# LoRa.net
KiCad netlist of a schematic drawn in Altium Designer
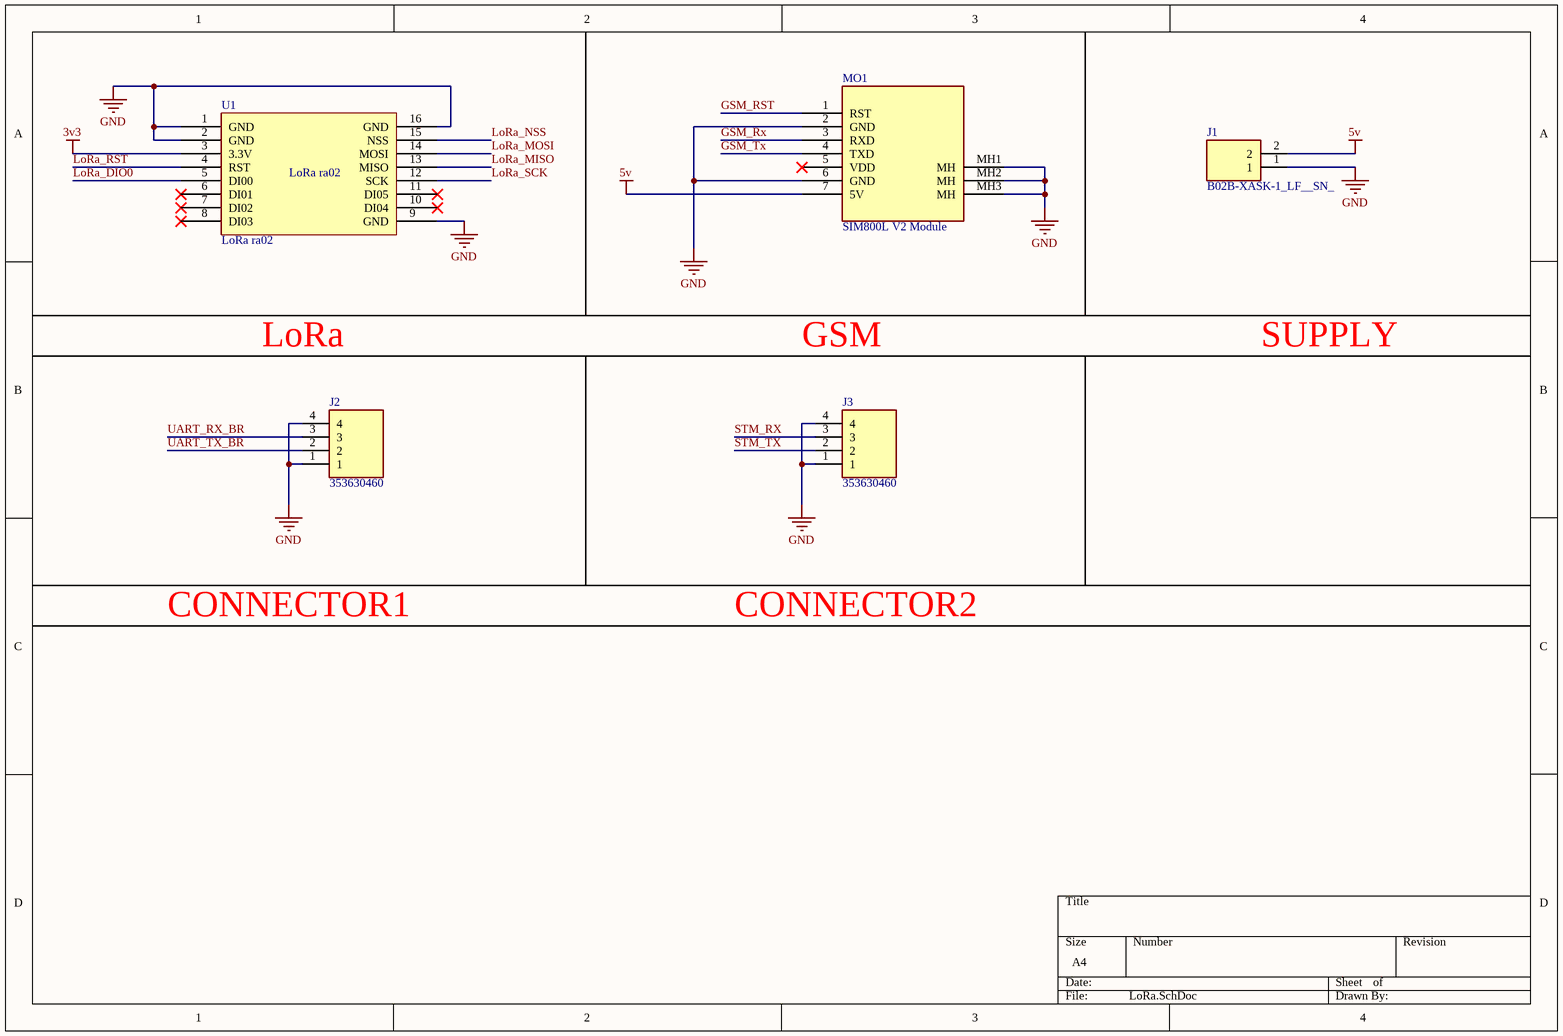
[diagram p0:  LoRa.SchDoc]

(export (version "E")
  (design (tool "Eeschema 10.0.6"))
  (components
    (comp (ref "J1")
      (value "B02B-XASK-1_LF__SN_")
      (footprint "SamacSys:SHDR2W60P0X250_1X2_750X640X880P")
      (description "Connector")
      (fields (field (name "MANUFACTURER_PART_NUMBER") "B02B-XASK-1(LF)(SN)"))
      (libsource (lib "*") (part "B02B-XASK-1_LF__SN_"))
    )
    (comp (ref "J2")
      (value "353630460")
      (footprint "SamacSys:353630460")
      (description "Connector")
      (libsource (lib "*") (part "353630460"))
    )
    (comp (ref "J3")
      (value "353630460")
      (footprint "SamacSys:353630460")
      (description "Connector")
      (libsource (lib "*") (part "353630460"))
    )
    (comp (ref "MO1")
      (value "SIM800L V2 Module")
      (footprint "SIM800LV2.0")
      (description "GSM Module")
      (libsource (lib "rf_components") (part "SIM800LV2.0"))
    )
    (comp (ref "U1")
      (value "LoRa ra02")
      (footprint "LoRa")
      (description "gg")
      (libsource (lib "rf_components") (part "LoRa ra02"))
    )
  )
  (nets
    (net (code "1") (name "/GSM_RST") (class "Default")
      (node (ref "MO1") (pin "1") (pinfunction "RST_1") (pintype "passive"))
    )
    (net (code "2") (name "/GSM_Rx") (class "Default")
      (node (ref "MO1") (pin "3") (pinfunction "RXD_3") (pintype "passive"))
    )
    (net (code "3") (name "/GSM_Tx") (class "Default")
      (node (ref "MO1") (pin "4") (pinfunction "TXD_4") (pintype "passive"))
    )
    (net (code "4") (name "/LoRa_DIO0") (class "Default")
      (node (ref "U1") (pin "5") (pinfunction "DI00_5") (pintype "passive"))
    )
    (net (code "5") (name "/LoRa_MISO") (class "Default")
      (node (ref "U1") (pin "13") (pinfunction "MISO_13") (pintype "passive"))
    )
    (net (code "6") (name "/LoRa_MOSI") (class "Default")
      (node (ref "U1") (pin "14") (pinfunction "MOSI_14") (pintype "passive"))
    )
    (net (code "7") (name "/LoRa_NSS") (class "Default")
      (node (ref "U1") (pin "15") (pinfunction "NSS_15") (pintype "passive"))
    )
    (net (code "8") (name "/LoRa_RST") (class "Default")
      (node (ref "U1") (pin "4") (pinfunction "RST_4") (pintype "passive"))
    )
    (net (code "9") (name "/LoRa_SCK") (class "Default")
      (node (ref "U1") (pin "12") (pinfunction "SCK_12") (pintype "passive"))
    )
    (net (code "10") (name "/STM_RX") (class "Default")
      (node (ref "J3") (pin "3") (pinfunction "3_3") (pintype "passive"))
    )
    (net (code "11") (name "/STM_TX") (class "Default")
      (node (ref "J3") (pin "2") (pinfunction "2_2") (pintype "passive"))
    )
    (net (code "12") (name "/UART_RX_BR") (class "Default")
      (node (ref "J2") (pin "3") (pinfunction "3_3") (pintype "passive"))
    )
    (net (code "13") (name "/UART_TX_BR") (class "Default")
      (node (ref "J2") (pin "2") (pinfunction "2_2") (pintype "passive"))
    )
    (net (code "14") (name "3v3") (class "Default")
      (node (ref "U1") (pin "3") (pinfunction "3.3V_3") (pintype "passive"))
    )
    (net (code "15") (name "5v") (class "Default")
      (node (ref "J1") (pin "2") (pinfunction "2_2") (pintype "passive"))
      (node (ref "MO1") (pin "7") (pinfunction "5V_7") (pintype "passive"))
    )
    (net (code "16") (name "GND") (class "Default")
      (node (ref "J1") (pin "1") (pinfunction "1_1") (pintype "passive"))
      (node (ref "J2") (pin "1") (pinfunction "1_1") (pintype "passive"))
      (node (ref "J2") (pin "4") (pinfunction "4_4") (pintype "passive"))
      (node (ref "J3") (pin "1") (pinfunction "1_1") (pintype "passive"))
      (node (ref "J3") (pin "4") (pinfunction "4_4") (pintype "passive"))
      (node (ref "MO1") (pin "2") (pinfunction "GND_2") (pintype "passive"))
      (node (ref "MO1") (pin "6") (pinfunction "GND_6") (pintype "passive"))
      (node (ref "MO1") (pin "MH1") (pinfunction "MH_MH1") (pintype "passive"))
      (node (ref "MO1") (pin "MH2") (pinfunction "MH_MH2") (pintype "passive"))
      (node (ref "MO1") (pin "MH3") (pinfunction "MH_MH3") (pintype "passive"))
      (node (ref "U1") (pin "1") (pinfunction "GND_1") (pintype "passive"))
      (node (ref "U1") (pin "16") (pinfunction "GND_16") (pintype "passive"))
      (node (ref "U1") (pin "2") (pinfunction "GND_2") (pintype "passive"))
      (node (ref "U1") (pin "9") (pinfunction "GND_9") (pintype "passive"))
    )
    (net (code "17") (name "unconnected-(MO1-VDD-Pad5)") (class "Default")
      (node (ref "MO1") (pin "5") (pinfunction "VDD_5") (pintype "passive+no_connect"))
    )
    (net (code "18") (name "unconnected-(U1-DI01-Pad6)") (class "Default")
      (node (ref "U1") (pin "6") (pinfunction "DI01_6") (pintype "passive+no_connect"))
    )
    (net (code "19") (name "unconnected-(U1-DI02-Pad7)") (class "Default")
      (node (ref "U1") (pin "7") (pinfunction "DI02_7") (pintype "passive+no_connect"))
    )
    (net (code "20") (name "unconnected-(U1-DI03-Pad8)") (class "Default")
      (node (ref "U1") (pin "8") (pinfunction "DI03_8") (pintype "passive+no_connect"))
    )
    (net (code "21") (name "unconnected-(U1-DI04-Pad10)") (class "Default")
      (node (ref "U1") (pin "10") (pinfunction "DI04_10") (pintype "passive+no_connect"))
    )
    (net (code "22") (name "unconnected-(U1-DI05-Pad11)") (class "Default")
      (node (ref "U1") (pin "11") (pinfunction "DI05_11") (pintype "passive+no_connect"))
    )
  )
)
